# Dual_Motor_Module.net
KiCad netlist of a schematic drawn in EAGLE
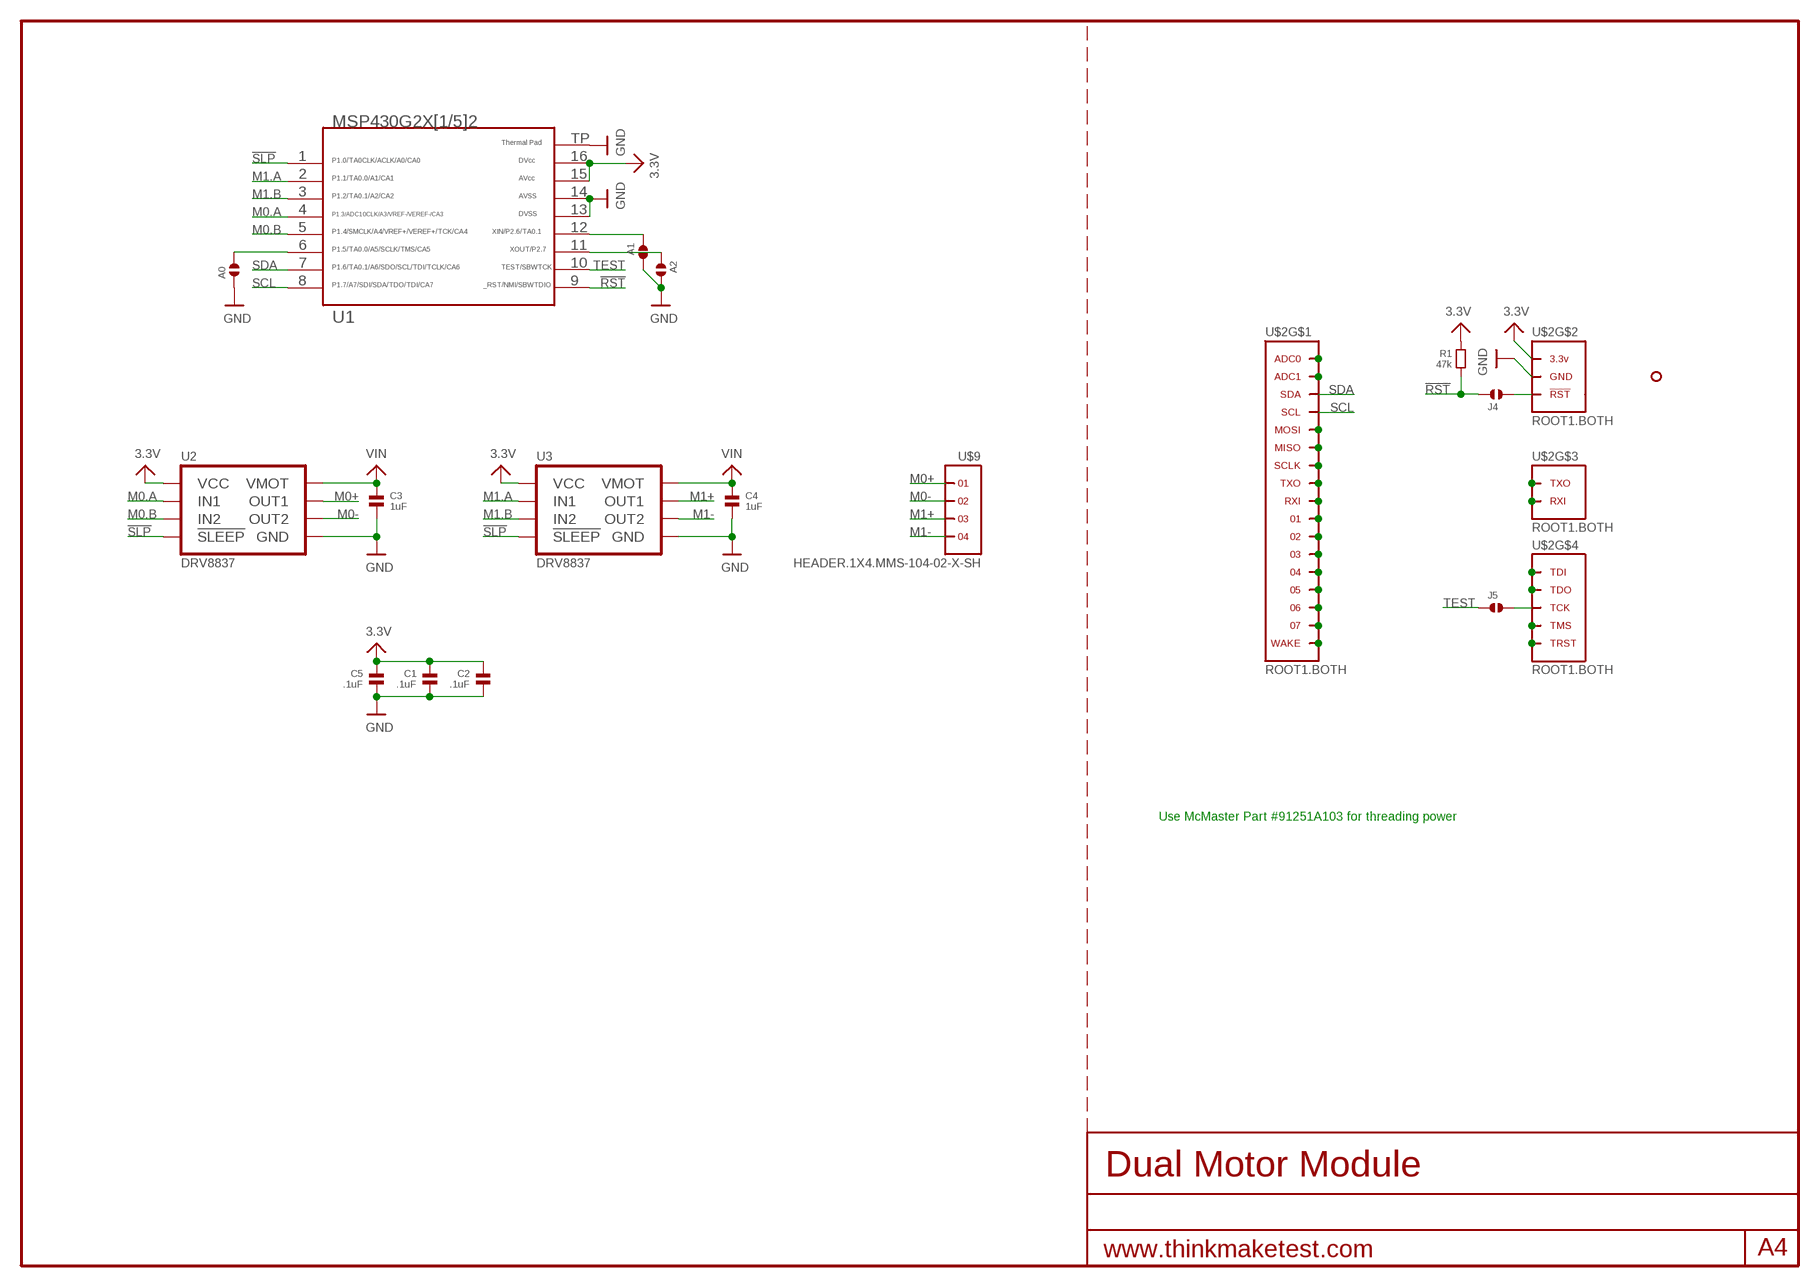
[diagram p0: schematic, sheet 1]

(export (version "E")
  (design (tool "Eeschema 10.0.6"))
  (components
    (comp (ref "A0")
      (value "SOLDERJUMPER.2.MED")
      (footprint "eagle-import:2.MED")
      (libsource (lib "eagle-import") (part "SOLDERJUMPER.2.MED"))
    )
    (comp (ref "A1")
      (value "SOLDERJUMPER.2.MED")
      (footprint "eagle-import:2.MED")
      (libsource (lib "eagle-import") (part "SOLDERJUMPER.2.MED"))
    )
    (comp (ref "A2")
      (value "SOLDERJUMPER.2.MED")
      (footprint "eagle-import:2.MED")
      (libsource (lib "eagle-import") (part "SOLDERJUMPER.2.MED"))
    )
    (comp (ref "C1")
      (value ".1uF")
      (footprint "eagle-import:0603")
      (libsource (lib "eagle-import") (part "CAPACITOR.0603"))
    )
    (comp (ref "C2")
      (value ".1uF")
      (footprint "eagle-import:0603")
      (libsource (lib "eagle-import") (part "CAPACITOR.0603"))
    )
    (comp (ref "C3")
      (value "1uF")
      (footprint "eagle-import:0603")
      (libsource (lib "eagle-import") (part "CAPACITOR.0603"))
    )
    (comp (ref "C4")
      (value "1uF")
      (footprint "eagle-import:0603")
      (libsource (lib "eagle-import") (part "CAPACITOR.0603"))
    )
    (comp (ref "C5")
      (value ".1uF")
      (footprint "eagle-import:0603")
      (libsource (lib "eagle-import") (part "CAPACITOR.0603"))
    )
    (comp (ref "J4")
      (value "SOLDERJUMPER.2.MED")
      (footprint "eagle-import:2.MED")
      (libsource (lib "eagle-import") (part "SOLDERJUMPER.2.MED"))
    )
    (comp (ref "J5")
      (value "SOLDERJUMPER.2.MED")
      (footprint "eagle-import:2.MED")
      (libsource (lib "eagle-import") (part "SOLDERJUMPER.2.MED"))
    )
    (comp (ref "R1")
      (value "47k")
      (footprint "eagle-import:0603")
      (libsource (lib "eagle-import") (part "RESISTOR.0603"))
    )
    (comp (ref "U$2")
      (value "ROOT1.BOTH")
      (footprint "eagle-import:ROOT1.BOTH")
      (libsource (lib "eagle-import") (part "ROOT1.BOTH"))
    )
    (comp (ref "U$4")
      (value "HOLE.#2")
      (footprint "eagle-import:#2")
      (libsource (lib "eagle-import") (part "HOLE.#2"))
    )
    (comp (ref "U$9")
      (value "HEADER.1X4.MMS-104-02-X-SH")
      (footprint "eagle-import:MMS-104-02-X-SH")
      (libsource (lib "eagle-import") (part "HEADER.1X4.MMS-104-02-X-SH"))
    )
    (comp (ref "U1")
      (value "MSP430G2452.QFN16")
      (footprint "eagle-import:RSA16")
      (libsource (lib "eagle-import") (part "G2X[1/5]2---RSA16"))
    )
    (comp (ref "U2")
      (value "DRV8837")
      (footprint "eagle-import:DSG")
      (libsource (lib "eagle-import") (part "DRV8837"))
    )
    (comp (ref "U3")
      (value "DRV8837")
      (footprint "eagle-import:DSG")
      (libsource (lib "eagle-import") (part "DRV8837"))
    )
  )
  (nets
    (net (code "1") (name "/M0+") (class "Default")
      (node (ref "U$9") (pin "1") (pinfunction "1_1") (pintype "bidirectional"))
      (node (ref "U$9") (pin "1@1") (pinfunction "1_1@1") (pintype "bidirectional"))
      (node (ref "U2") (pin "2") (pinfunction "OUT1_2") (pintype "bidirectional"))
    )
    (net (code "2") (name "/M0-") (class "Default")
      (node (ref "U$9") (pin "2") (pinfunction "2_2") (pintype "bidirectional"))
      (node (ref "U$9") (pin "2@1") (pinfunction "2_2@1") (pintype "bidirectional"))
      (node (ref "U2") (pin "3") (pinfunction "OUT2_3") (pintype "bidirectional"))
    )
    (net (code "3") (name "/M0.A") (class "Default")
      (node (ref "U1") (pin "4") (pinfunction "4_4") (pintype "bidirectional"))
      (node (ref "U2") (pin "6") (pinfunction "IN1_6") (pintype "bidirectional"))
    )
    (net (code "4") (name "/M0.B") (class "Default")
      (node (ref "U1") (pin "5") (pinfunction "5_5") (pintype "bidirectional"))
      (node (ref "U2") (pin "5") (pinfunction "IN2_5") (pintype "bidirectional"))
    )
    (net (code "5") (name "/M1+") (class "Default")
      (node (ref "U$9") (pin "3") (pinfunction "3_3") (pintype "bidirectional"))
      (node (ref "U$9") (pin "3@1") (pinfunction "3_3@1") (pintype "bidirectional"))
      (node (ref "U3") (pin "2") (pinfunction "OUT1_2") (pintype "bidirectional"))
    )
    (net (code "6") (name "/M1-") (class "Default")
      (node (ref "U$9") (pin "4") (pinfunction "4_4") (pintype "bidirectional"))
      (node (ref "U$9") (pin "4@1") (pinfunction "4_4@1") (pintype "bidirectional"))
      (node (ref "U3") (pin "3") (pinfunction "OUT2_3") (pintype "bidirectional"))
    )
    (net (code "7") (name "/M1.A") (class "Default")
      (node (ref "U1") (pin "2") (pinfunction "2_2") (pintype "bidirectional"))
      (node (ref "U3") (pin "6") (pinfunction "IN1_6") (pintype "bidirectional"))
    )
    (net (code "8") (name "/M1.B") (class "Default")
      (node (ref "U1") (pin "3") (pinfunction "3_3") (pintype "bidirectional"))
      (node (ref "U3") (pin "5") (pinfunction "IN2_5") (pintype "bidirectional"))
    )
    (net (code "9") (name "/SCL") (class "Default")
      (node (ref "U$2") (pin "SCL") (pinfunction "SCL_SCL") (pintype "bidirectional"))
      (node (ref "U$2") (pin "SCL@1") (pinfunction "SCL_SCL@1") (pintype "bidirectional"))
      (node (ref "U$2") (pin "SCL@VIA") (pinfunction "SCL_SCL@VIA") (pintype "bidirectional"))
      (node (ref "U1") (pin "8") (pinfunction "8_8") (pintype "bidirectional"))
    )
    (net (code "10") (name "/SDA") (class "Default")
      (node (ref "U$2") (pin "SDA") (pinfunction "SDA_SDA") (pintype "bidirectional"))
      (node (ref "U$2") (pin "SDA@1") (pinfunction "SDA_SDA@1") (pintype "bidirectional"))
      (node (ref "U$2") (pin "SDA@VIA") (pinfunction "SDA_SDA@VIA") (pintype "bidirectional"))
      (node (ref "U1") (pin "7") (pinfunction "7_7") (pintype "bidirectional"))
    )
    (net (code "11") (name "/TEST") (class "Default")
      (node (ref "J5") (pin "1") (pinfunction "1_1") (pintype "bidirectional"))
      (node (ref "U1") (pin "10") (pinfunction "10_10") (pintype "bidirectional"))
    )
    (net (code "12") (name "/~{RST}") (class "Default")
      (node (ref "J4") (pin "1") (pinfunction "1_1") (pintype "bidirectional"))
      (node (ref "R1") (pin "2") (pinfunction "2_2") (pintype "bidirectional"))
      (node (ref "U1") (pin "9") (pinfunction "9_9") (pintype "bidirectional"))
    )
    (net (code "13") (name "/~{SLP}") (class "Default")
      (node (ref "U1") (pin "1") (pinfunction "1_1") (pintype "bidirectional"))
      (node (ref "U2") (pin "7") (pinfunction "~{SLEEP}_7") (pintype "bidirectional"))
      (node (ref "U3") (pin "7") (pinfunction "~{SLEEP}_7") (pintype "bidirectional"))
    )
    (net (code "14") (name "3.3V") (class "Default")
      (node (ref "C1") (pin "1") (pinfunction "1_1") (pintype "bidirectional"))
      (node (ref "C2") (pin "1") (pinfunction "1_1") (pintype "bidirectional"))
      (node (ref "C5") (pin "1") (pinfunction "1_1") (pintype "bidirectional"))
      (node (ref "R1") (pin "1") (pinfunction "1_1") (pintype "bidirectional"))
      (node (ref "U$2") (pin "3.3V@1") (pinfunction "3.3V_3.3V@1") (pintype "bidirectional"))
      (node (ref "U$2") (pin "3.3V@10") (pinfunction "3.3V_3.3V@10") (pintype "bidirectional"))
      (node (ref "U$2") (pin "3.3V@11") (pinfunction "3.3V_3.3V@11") (pintype "bidirectional"))
      (node (ref "U$2") (pin "3.3V@12") (pinfunction "3.3V_3.3V@12") (pintype "bidirectional"))
      (node (ref "U$2") (pin "3.3V@13") (pinfunction "3.3V_3.3V@13") (pintype "bidirectional"))
      (node (ref "U$2") (pin "3.3V@14") (pinfunction "3.3V_3.3V@14") (pintype "bidirectional"))
      (node (ref "U$2") (pin "3.3V@15") (pinfunction "3.3V_3.3V@15") (pintype "bidirectional"))
      (node (ref "U$2") (pin "3.3V@16") (pinfunction "3.3V_3.3V@16") (pintype "bidirectional"))
      (node (ref "U$2") (pin "3.3V@17") (pinfunction "3.3V_3.3V@17") (pintype "bidirectional"))
      (node (ref "U$2") (pin "3.3V@18") (pinfunction "3.3V_3.3V@18") (pintype "bidirectional"))
      (node (ref "U$2") (pin "3.3V@19") (pinfunction "3.3V_3.3V@19") (pintype "bidirectional"))
      (node (ref "U$2") (pin "3.3V@2") (pinfunction "3.3V_3.3V@2") (pintype "bidirectional"))
      (node (ref "U$2") (pin "3.3V@20") (pinfunction "3.3V_3.3V@20") (pintype "bidirectional"))
      (node (ref "U$2") (pin "3.3V@21") (pinfunction "3.3V_3.3V@21") (pintype "bidirectional"))
      (node (ref "U$2") (pin "3.3V@22") (pinfunction "3.3V_3.3V@22") (pintype "bidirectional"))
      (node (ref "U$2") (pin "3.3V@23") (pinfunction "3.3V_3.3V@23") (pintype "bidirectional"))
      (node (ref "U$2") (pin "3.3V@24") (pinfunction "3.3V_3.3V@24") (pintype "bidirectional"))
      (node (ref "U$2") (pin "3.3V@3") (pinfunction "3.3V_3.3V@3") (pintype "bidirectional"))
      (node (ref "U$2") (pin "3.3V@4") (pinfunction "3.3V_3.3V@4") (pintype "bidirectional"))
      (node (ref "U$2") (pin "3.3V@5") (pinfunction "3.3V_3.3V@5") (pintype "bidirectional"))
      (node (ref "U$2") (pin "3.3V@6") (pinfunction "3.3V_3.3V@6") (pintype "bidirectional"))
      (node (ref "U$2") (pin "3.3V@7") (pinfunction "3.3V_3.3V@7") (pintype "bidirectional"))
      (node (ref "U$2") (pin "3.3V@8") (pinfunction "3.3V_3.3V@8") (pintype "bidirectional"))
      (node (ref "U$2") (pin "3.3V@9") (pinfunction "3.3V_3.3V@9") (pintype "bidirectional"))
      (node (ref "U$2") (pin "3.3V@VIA") (pinfunction "3.3V_3.3V@VIA") (pintype "bidirectional"))
      (node (ref "U1") (pin "15") (pinfunction "15_15") (pintype "bidirectional"))
      (node (ref "U1") (pin "16") (pinfunction "16_16") (pintype "bidirectional"))
      (node (ref "U2") (pin "8") (pinfunction "VCC_8") (pintype "bidirectional"))
      (node (ref "U3") (pin "8") (pinfunction "VCC_8") (pintype "bidirectional"))
    )
    (net (code "15") (name "GND") (class "Default")
      (node (ref "A0") (pin "1") (pinfunction "1_1") (pintype "bidirectional"))
      (node (ref "A1") (pin "2") (pinfunction "2_2") (pintype "bidirectional"))
      (node (ref "A2") (pin "2") (pinfunction "2_2") (pintype "bidirectional"))
      (node (ref "C1") (pin "2") (pinfunction "2_2") (pintype "bidirectional"))
      (node (ref "C2") (pin "2") (pinfunction "2_2") (pintype "bidirectional"))
      (node (ref "C3") (pin "2") (pinfunction "2_2") (pintype "bidirectional"))
      (node (ref "C4") (pin "2") (pinfunction "2_2") (pintype "bidirectional"))
      (node (ref "C5") (pin "2") (pinfunction "2_2") (pintype "bidirectional"))
      (node (ref "U$2") (pin "GND@1") (pinfunction "GND_GND@1") (pintype "bidirectional"))
      (node (ref "U$2") (pin "GND@10") (pinfunction "GND_GND@10") (pintype "bidirectional"))
      (node (ref "U$2") (pin "GND@11") (pinfunction "GND_GND@11") (pintype "bidirectional"))
      (node (ref "U$2") (pin "GND@12") (pinfunction "GND_GND@12") (pintype "bidirectional"))
      (node (ref "U$2") (pin "GND@13") (pinfunction "GND_GND@13") (pintype "bidirectional"))
      (node (ref "U$2") (pin "GND@14") (pinfunction "GND_GND@14") (pintype "bidirectional"))
      (node (ref "U$2") (pin "GND@15") (pinfunction "GND_GND@15") (pintype "bidirectional"))
      (node (ref "U$2") (pin "GND@16") (pinfunction "GND_GND@16") (pintype "bidirectional"))
      (node (ref "U$2") (pin "GND@17") (pinfunction "GND_GND@17") (pintype "bidirectional"))
      (node (ref "U$2") (pin "GND@18") (pinfunction "GND_GND@18") (pintype "bidirectional"))
      (node (ref "U$2") (pin "GND@19") (pinfunction "GND_GND@19") (pintype "bidirectional"))
      (node (ref "U$2") (pin "GND@2") (pinfunction "GND_GND@2") (pintype "bidirectional"))
      (node (ref "U$2") (pin "GND@20") (pinfunction "GND_GND@20") (pintype "bidirectional"))
      (node (ref "U$2") (pin "GND@21") (pinfunction "GND_GND@21") (pintype "bidirectional"))
      (node (ref "U$2") (pin "GND@22") (pinfunction "GND_GND@22") (pintype "bidirectional"))
      (node (ref "U$2") (pin "GND@23") (pinfunction "GND_GND@23") (pintype "bidirectional"))
      (node (ref "U$2") (pin "GND@24") (pinfunction "GND_GND@24") (pintype "bidirectional"))
      (node (ref "U$2") (pin "GND@25") (pinfunction "GND_GND@25") (pintype "bidirectional"))
      (node (ref "U$2") (pin "GND@26") (pinfunction "GND_GND@26") (pintype "bidirectional"))
      (node (ref "U$2") (pin "GND@3") (pinfunction "GND_GND@3") (pintype "bidirectional"))
      (node (ref "U$2") (pin "GND@4") (pinfunction "GND_GND@4") (pintype "bidirectional"))
      (node (ref "U$2") (pin "GND@5") (pinfunction "GND_GND@5") (pintype "bidirectional"))
      (node (ref "U$2") (pin "GND@6") (pinfunction "GND_GND@6") (pintype "bidirectional"))
      (node (ref "U$2") (pin "GND@7") (pinfunction "GND_GND@7") (pintype "bidirectional"))
      (node (ref "U$2") (pin "GND@8") (pinfunction "GND_GND@8") (pintype "bidirectional"))
      (node (ref "U$2") (pin "GND@9") (pinfunction "GND_GND@9") (pintype "bidirectional"))
      (node (ref "U$2") (pin "GND@VIA") (pinfunction "GND_GND@VIA") (pintype "bidirectional"))
      (node (ref "U1") (pin "13") (pinfunction "13_13") (pintype "bidirectional"))
      (node (ref "U1") (pin "14") (pinfunction "14_14") (pintype "bidirectional"))
      (node (ref "U1") (pin "TP") (pinfunction "TP_TP") (pintype "bidirectional"))
      (node (ref "U2") (pin "4") (pinfunction "GND_4") (pintype "bidirectional"))
      (node (ref "U2") (pin "PAD") (pinfunction "GND_PAD") (pintype "bidirectional"))
      (node (ref "U3") (pin "4") (pinfunction "GND_4") (pintype "bidirectional"))
      (node (ref "U3") (pin "PAD") (pinfunction "GND_PAD") (pintype "bidirectional"))
    )
    (net (code "16") (name "Net-(A0-Pad2)") (class "Default")
      (node (ref "A0") (pin "2") (pinfunction "2_2") (pintype "bidirectional"))
      (node (ref "U1") (pin "6") (pinfunction "6_6") (pintype "bidirectional"))
    )
    (net (code "17") (name "Net-(A1-Pad1)") (class "Default")
      (node (ref "A1") (pin "1") (pinfunction "1_1") (pintype "bidirectional"))
      (node (ref "U1") (pin "12") (pinfunction "12_12") (pintype "bidirectional"))
    )
    (net (code "18") (name "Net-(A2-Pad1)") (class "Default")
      (node (ref "A2") (pin "1") (pinfunction "1_1") (pintype "bidirectional"))
      (node (ref "U1") (pin "11") (pinfunction "11_11") (pintype "bidirectional"))
    )
    (net (code "19") (name "Net-(J4-Pad2)") (class "Default")
      (node (ref "J4") (pin "2") (pinfunction "2_2") (pintype "bidirectional"))
      (node (ref "U$2") (pin "RST") (pinfunction "~{RST}_RST") (pintype "bidirectional"))
      (node (ref "U$2") (pin "RST@1") (pinfunction "~{RST}_RST@1") (pintype "bidirectional"))
      (node (ref "U$2") (pin "RST@VIA") (pinfunction "~{RST}_RST@VIA") (pintype "bidirectional"))
    )
    (net (code "20") (name "Net-(J5-Pad2)") (class "Default")
      (node (ref "J5") (pin "2") (pinfunction "2_2") (pintype "bidirectional"))
      (node (ref "U$2") (pin "TCK") (pinfunction "TCK_TCK") (pintype "bidirectional"))
      (node (ref "U$2") (pin "TCK@1") (pinfunction "TCK_TCK@1") (pintype "bidirectional"))
      (node (ref "U$2") (pin "TCK@VIA") (pinfunction "TCK_TCK@VIA") (pintype "bidirectional"))
    )
    (net (code "21") (name "Net-(U$2-Pad01)") (class "Default")
      (node (ref "U$2") (pin "01") (pinfunction "01_01") (pintype "bidirectional"))
      (node (ref "U$2") (pin "01@1") (pinfunction "01_01@1") (pintype "bidirectional"))
      (node (ref "U$2") (pin "01@VIA") (pinfunction "01_01@VIA") (pintype "bidirectional"))
    )
    (net (code "22") (name "Net-(U$2-Pad02)") (class "Default")
      (node (ref "U$2") (pin "02") (pinfunction "02_02") (pintype "bidirectional"))
      (node (ref "U$2") (pin "02@1") (pinfunction "02_02@1") (pintype "bidirectional"))
      (node (ref "U$2") (pin "02@VIA") (pinfunction "02_02@VIA") (pintype "bidirectional"))
    )
    (net (code "23") (name "Net-(U$2-Pad03)") (class "Default")
      (node (ref "U$2") (pin "03") (pinfunction "03_03") (pintype "bidirectional"))
      (node (ref "U$2") (pin "03@1") (pinfunction "03_03@1") (pintype "bidirectional"))
      (node (ref "U$2") (pin "03@VIA") (pinfunction "03_03@VIA") (pintype "bidirectional"))
    )
    (net (code "24") (name "Net-(U$2-Pad04)") (class "Default")
      (node (ref "U$2") (pin "04") (pinfunction "04_04") (pintype "bidirectional"))
      (node (ref "U$2") (pin "04@1") (pinfunction "04_04@1") (pintype "bidirectional"))
      (node (ref "U$2") (pin "04@VIA") (pinfunction "04_04@VIA") (pintype "bidirectional"))
    )
    (net (code "25") (name "Net-(U$2-Pad05)") (class "Default")
      (node (ref "U$2") (pin "05") (pinfunction "05_05") (pintype "bidirectional"))
      (node (ref "U$2") (pin "05@1") (pinfunction "05_05@1") (pintype "bidirectional"))
      (node (ref "U$2") (pin "05@VIA") (pinfunction "05_05@VIA") (pintype "bidirectional"))
    )
    (net (code "26") (name "Net-(U$2-Pad06)") (class "Default")
      (node (ref "U$2") (pin "06") (pinfunction "06_06") (pintype "bidirectional"))
      (node (ref "U$2") (pin "06@1") (pinfunction "06_06@1") (pintype "bidirectional"))
      (node (ref "U$2") (pin "06@VIA") (pinfunction "06_06@VIA") (pintype "bidirectional"))
    )
    (net (code "27") (name "Net-(U$2-Pad07)") (class "Default")
      (node (ref "U$2") (pin "07") (pinfunction "07_07") (pintype "bidirectional"))
      (node (ref "U$2") (pin "07@1") (pinfunction "07_07@1") (pintype "bidirectional"))
      (node (ref "U$2") (pin "07@VIA") (pinfunction "07_07@VIA") (pintype "bidirectional"))
    )
    (net (code "28") (name "Net-(U$2-PadADC0)") (class "Default")
      (node (ref "U$2") (pin "ADC0") (pinfunction "ADC0_ADC0") (pintype "bidirectional"))
      (node (ref "U$2") (pin "ADC0@1") (pinfunction "ADC0_ADC0@1") (pintype "bidirectional"))
      (node (ref "U$2") (pin "ADC0@VIA") (pinfunction "ADC0_ADC0@VIA") (pintype "bidirectional"))
    )
    (net (code "29") (name "Net-(U$2-PadADC1)") (class "Default")
      (node (ref "U$2") (pin "ADC1") (pinfunction "ADC1_ADC1") (pintype "bidirectional"))
      (node (ref "U$2") (pin "ADC1@1") (pinfunction "ADC1_ADC1@1") (pintype "bidirectional"))
      (node (ref "U$2") (pin "ADC1@VIA") (pinfunction "ADC1_ADC1@VIA") (pintype "bidirectional"))
    )
    (net (code "30") (name "Net-(U$2-PadMISO)") (class "Default")
      (node (ref "U$2") (pin "MISO") (pinfunction "MISO_MISO") (pintype "bidirectional"))
      (node (ref "U$2") (pin "MISO@1") (pinfunction "MISO_MISO@1") (pintype "bidirectional"))
      (node (ref "U$2") (pin "MISO@VIA") (pinfunction "MISO_MISO@VIA") (pintype "bidirectional"))
    )
    (net (code "31") (name "Net-(U$2-PadMOSI)") (class "Default")
      (node (ref "U$2") (pin "MOSI") (pinfunction "MOSI_MOSI") (pintype "bidirectional"))
      (node (ref "U$2") (pin "MOSI@1") (pinfunction "MOSI_MOSI@1") (pintype "bidirectional"))
      (node (ref "U$2") (pin "MOSI@VIA") (pinfunction "MOSI_MOSI@VIA") (pintype "bidirectional"))
    )
    (net (code "32") (name "Net-(U$2-PadRXI)") (class "Default")
      (node (ref "U$2") (pin "RXI") (pinfunction "RXI_RXI") (pintype "bidirectional"))
      (node (ref "U$2") (pin "RXI@1") (pinfunction "RXI_RXI@1") (pintype "bidirectional"))
      (node (ref "U$2") (pin "RXI@VIA") (pinfunction "RXI_RXI@VIA") (pintype "bidirectional"))
    )
    (net (code "33") (name "Net-(U$2-PadSCLK)") (class "Default")
      (node (ref "U$2") (pin "SCLK") (pinfunction "SCLK_SCLK") (pintype "bidirectional"))
      (node (ref "U$2") (pin "SCLK@1") (pinfunction "SCLK_SCLK@1") (pintype "bidirectional"))
      (node (ref "U$2") (pin "SCLK@VIA") (pinfunction "SCLK_SCLK@VIA") (pintype "bidirectional"))
    )
    (net (code "34") (name "Net-(U$2-PadTDI)") (class "Default")
      (node (ref "U$2") (pin "TDI") (pinfunction "TDI_TDI") (pintype "bidirectional"))
      (node (ref "U$2") (pin "TDI@1") (pinfunction "TDI_TDI@1") (pintype "bidirectional"))
      (node (ref "U$2") (pin "TDI@VIA") (pinfunction "TDI_TDI@VIA") (pintype "bidirectional"))
    )
    (net (code "35") (name "Net-(U$2-PadTDO)") (class "Default")
      (node (ref "U$2") (pin "TDO") (pinfunction "TDO_TDO") (pintype "bidirectional"))
      (node (ref "U$2") (pin "TDO@1") (pinfunction "TDO_TDO@1") (pintype "bidirectional"))
      (node (ref "U$2") (pin "TDO@VIA") (pinfunction "TDO_TDO@VIA") (pintype "bidirectional"))
    )
    (net (code "36") (name "Net-(U$2-PadTMS)") (class "Default")
      (node (ref "U$2") (pin "TMS") (pinfunction "TMS_TMS") (pintype "bidirectional"))
      (node (ref "U$2") (pin "TMS@1") (pinfunction "TMS_TMS@1") (pintype "bidirectional"))
      (node (ref "U$2") (pin "TMS@VIA") (pinfunction "TMS_TMS@VIA") (pintype "bidirectional"))
    )
    (net (code "37") (name "Net-(U$2-PadTRST)") (class "Default")
      (node (ref "U$2") (pin "TRST") (pinfunction "TRST_TRST") (pintype "bidirectional"))
      (node (ref "U$2") (pin "TRST@1") (pinfunction "TRST_TRST@1") (pintype "bidirectional"))
      (node (ref "U$2") (pin "TRST@VIA") (pinfunction "TRST_TRST@VIA") (pintype "bidirectional"))
    )
    (net (code "38") (name "Net-(U$2-PadTXO)") (class "Default")
      (node (ref "U$2") (pin "TXO") (pinfunction "TXO_TXO") (pintype "bidirectional"))
      (node (ref "U$2") (pin "TXO@1") (pinfunction "TXO_TXO@1") (pintype "bidirectional"))
      (node (ref "U$2") (pin "TXO@VIA") (pinfunction "TXO_TXO@VIA") (pintype "bidirectional"))
    )
    (net (code "39") (name "Net-(U$2-PadWAKE)") (class "Default")
      (node (ref "U$2") (pin "WAKE") (pinfunction "WAKE_WAKE") (pintype "bidirectional"))
      (node (ref "U$2") (pin "WAKE@1") (pinfunction "WAKE_WAKE@1") (pintype "bidirectional"))
      (node (ref "U$2") (pin "WAKE@VIA") (pinfunction "WAKE_WAKE@VIA") (pintype "bidirectional"))
    )
    (net (code "40") (name "Net-(U$2C-RXI-PadRXI.DBG)") (class "Default")
      (node (ref "U$2") (pin "RXI.DBG") (pinfunction "RXI_RXI.DBG") (pintype "bidirectional"))
      (node (ref "U$2") (pin "RXI.DBG@1") (pinfunction "RXI_RXI.DBG@1") (pintype "bidirectional"))
      (node (ref "U$2") (pin "RXI.DBG@VIA") (pinfunction "RXI_RXI.DBG@VIA") (pintype "bidirectional"))
    )
    (net (code "41") (name "Net-(U$2C-TXO-PadTXO.DBG)") (class "Default")
      (node (ref "U$2") (pin "TXO.DBG") (pinfunction "TXO_TXO.DBG") (pintype "bidirectional"))
      (node (ref "U$2") (pin "TXO.DBG@1") (pinfunction "TXO_TXO.DBG@1") (pintype "bidirectional"))
      (node (ref "U$2") (pin "TXO.DBG@VIA") (pinfunction "TXO_TXO.DBG@VIA") (pintype "bidirectional"))
    )
    (net (code "42") (name "VIN") (class "Default")
      (node (ref "C3") (pin "1") (pinfunction "1_1") (pintype "bidirectional"))
      (node (ref "C4") (pin "1") (pinfunction "1_1") (pintype "bidirectional"))
      (node (ref "U2") (pin "1") (pinfunction "VMOT_1") (pintype "bidirectional"))
      (node (ref "U3") (pin "1") (pinfunction "VMOT_1") (pintype "bidirectional"))
    )
  )
)
